# Vertical.net
KiCad netlist of a schematic drawn in Altium Designer
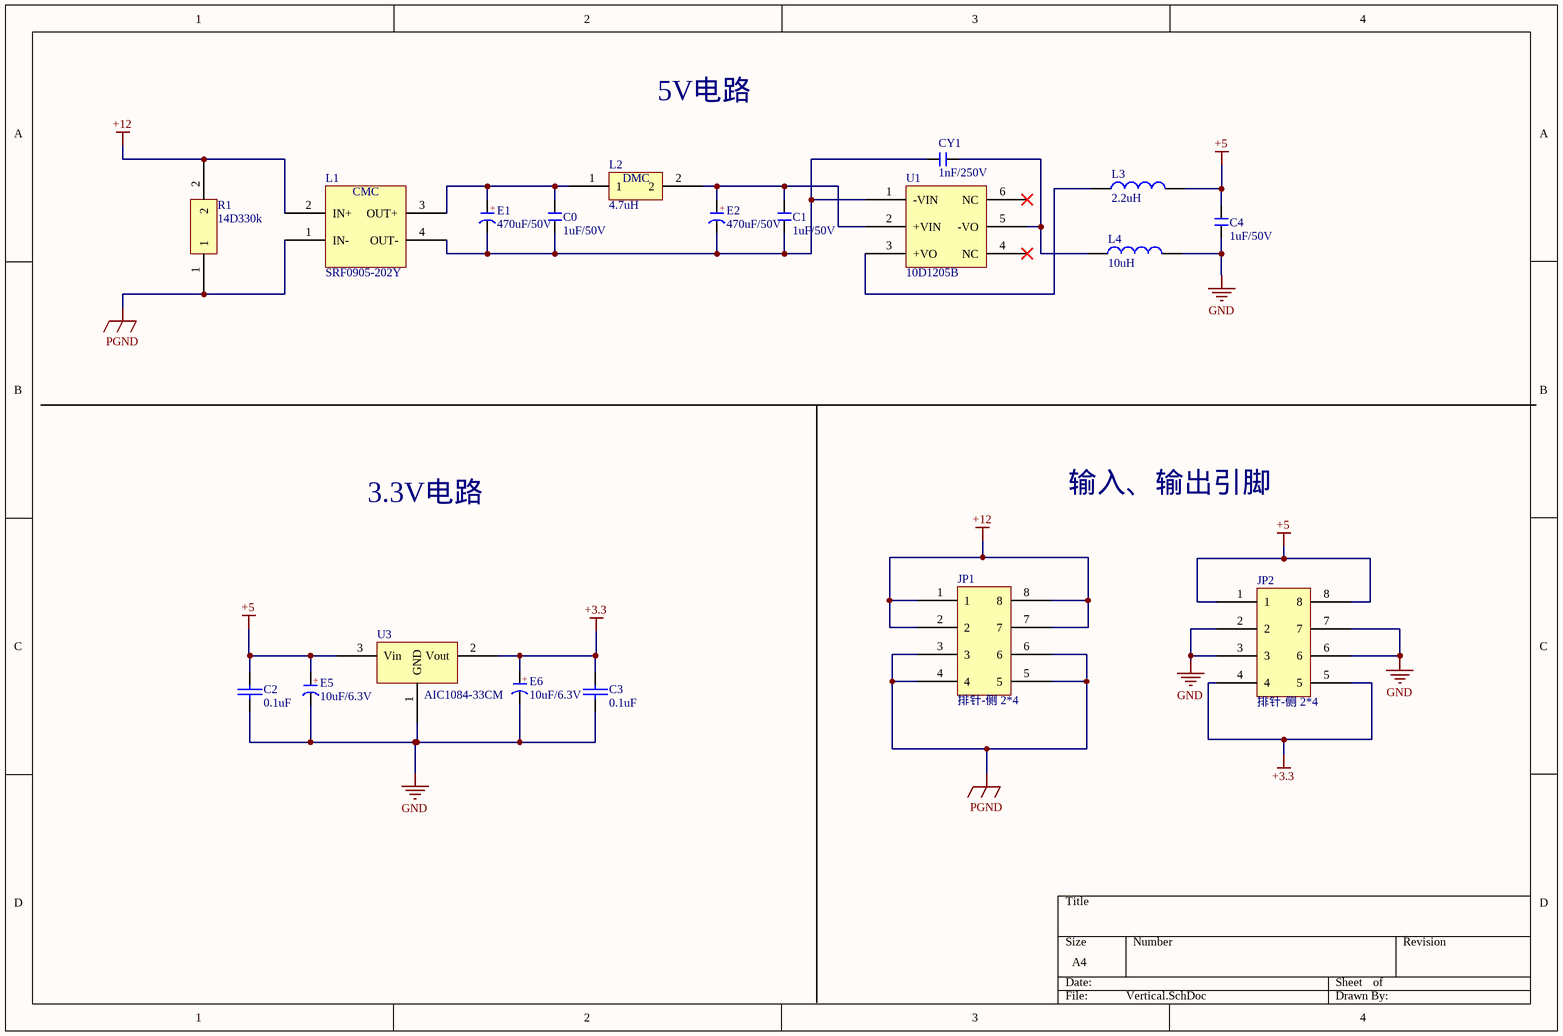
[diagram p0: Vertical.SchDoc]

(export (version "E")
  (design (tool "Eeschema 10.0.6"))
  (components
    (comp (ref "C0")
      (value "1uF/50V")
      (footprint "CC 2.2*5")
      (description "直插瓷片电容")
      (fields (field (name "版权归属") "源创客"))
      (libsource (lib "3.1   - 电阻-电容-电感") (part "C-CC"))
    )
    (comp (ref "C1")
      (value "1uF/50V")
      (footprint "CC 2.2*5")
      (description "直插瓷片电容")
      (fields (field (name "版权归属") "源创客"))
      (libsource (lib "3.1   - 电阻-电容-电感") (part "C-CC"))
    )
    (comp (ref "C2")
      (value "0.1uF")
      (footprint "0603C")
      (description "无极性电容")
      (libsource (lib "电容") (part "CAP"))
    )
    (comp (ref "C3")
      (value "0.1uF")
      (footprint "0603C")
      (description "无极性电容")
      (libsource (lib "电容") (part "CAP"))
    )
    (comp (ref "C4")
      (value "1uF/50V")
      (footprint "CC 2.2*5")
      (description "直插瓷片电容")
      (fields (field (name "版权归属") "源创客"))
      (libsource (lib "3.1   - 电阻-电容-电感") (part "C-CC"))
    )
    (comp (ref "CY1")
      (value "1nF/250V")
      (footprint "CY 7.5*10*4")
      (description "高压陶瓷电容，Y电容")
      (fields (field (name "版权归属") "源创客"))
      (libsource (lib "3.1   - 电阻-电容-电感") (part "C-CY"))
    )
    (comp (ref "E1")
      (value "470uF/50V")
      (footprint "CM G(12.5*13.5)")
      (description "贴片电解电容")
      (fields (field (name "版权归属") "源创客"))
      (libsource (lib "3.1   - 电阻-电容-电感") (part "C-CM"))
    )
    (comp (ref "E2")
      (value "470uF/50V")
      (footprint "CM G(12.5*13.5)")
      (description "贴片电解电容")
      (fields (field (name "版权归属") "源创客"))
      (libsource (lib "3.1   - 电阻-电容-电感") (part "C-CM"))
    )
    (comp (ref "E5")
      (value "10uF/6.3V")
      (footprint "CD A(3216)")
      (description "贴片钽电容")
      (fields (field (name "版权归属") "源创客"))
      (libsource (lib "3.1   - 电阻-电容-电感") (part "C-CD"))
    )
    (comp (ref "E6")
      (value "10uF/6.3V")
      (footprint "CD A(3216)")
      (description "贴片钽电容")
      (fields (field (name "版权归属") "源创客"))
      (libsource (lib "3.1   - 电阻-电容-电感") (part "C-CD"))
    )
    (comp (ref "JP1") (value "排针-侧 2*4") (footprint "排针-侧 2*4") (libsource (lib "power") (part "排针-侧 2*4")))
    (comp (ref "JP2") (value "排针-侧 2*4") (footprint "排针-侧 2*4") (libsource (lib "power") (part "排针-侧 2*4")))
    (comp (ref "L1")
      (value "SRF0905-202Y")
      (footprint "SRF0905")
      (description "共模电感")
      (libsource (lib "power") (part "SRF0905-202Y"))
    )
    (comp (ref "L2")
      (value "4.7uH")
      (footprint "NR5020")
      (description "差模电感")
      (libsource (lib "power") (part "DML-5020"))
    )
    (comp (ref "L3")
      (value "2.2uH")
      (footprint "L 0805")
      (description "小功率贴片电感")
      (fields (field (name "版权归属") "源创客"))
      (libsource (lib "3.1   - 电阻-电容-电感") (part "L"))
    )
    (comp (ref "L4")
      (value "10uH")
      (footprint "L 0805")
      (description "小功率贴片电感")
      (fields (field (name "版权归属") "源创客"))
      (libsource (lib "3.1   - 电阻-电容-电感") (part "L"))
    )
    (comp (ref "R1") (value "14D330k") (footprint "14D330k") (libsource (lib "power") (part "14D330k")))
    (comp (ref "U1") (value "10D1205B") (footprint "10D1205B") (libsource (lib "power") (part "10D1205B")))
    (comp (ref "U3")
      (value "AIC1084-33CM")
      (footprint "TO263-3B")
      (libsource (lib "power") (part "AIC1084-33CM"))
    )
  )
  (nets
    (net (code "1") (name "+3.3") (class "Default")
      (node (ref "C3") (pin "1") (pinfunction "1_1") (pintype "passive"))
      (node (ref "E6") (pin "1") (pinfunction "A_1") (pintype "passive"))
      (node (ref "JP2") (pin "4") (pinfunction "4_4") (pintype "passive"))
      (node (ref "JP2") (pin "5") (pinfunction "5_5") (pintype "passive"))
      (node (ref "U3") (pin "2") (pinfunction "Vout_2") (pintype "passive"))
    )
    (net (code "2") (name "+5") (class "Default")
      (node (ref "C2") (pin "2") (pinfunction "2_2") (pintype "passive"))
      (node (ref "C4") (pin "1") (pinfunction "1_1") (pintype "passive"))
      (node (ref "E5") (pin "1") (pinfunction "A_1") (pintype "passive"))
      (node (ref "JP2") (pin "1") (pinfunction "1_1") (pintype "passive"))
      (node (ref "JP2") (pin "8") (pinfunction "8_8") (pintype "passive"))
      (node (ref "L3") (pin "2") (pinfunction "2_2") (pintype "passive"))
      (node (ref "U3") (pin "3") (pinfunction "Vin_3") (pintype "passive"))
    )
    (net (code "3") (name "+12") (class "Default")
      (node (ref "JP1") (pin "1") (pinfunction "1_1") (pintype "passive"))
      (node (ref "JP1") (pin "2") (pinfunction "2_2") (pintype "passive"))
      (node (ref "JP1") (pin "7") (pinfunction "7_7") (pintype "passive"))
      (node (ref "JP1") (pin "8") (pinfunction "8_8") (pintype "passive"))
      (node (ref "L1") (pin "2") (pinfunction "IN+_2") (pintype "passive"))
      (node (ref "R1") (pin "2") (pinfunction "2_2") (pintype "passive"))
    )
    (net (code "4") (name "GND") (class "Default")
      (node (ref "C2") (pin "1") (pinfunction "1_1") (pintype "passive"))
      (node (ref "C3") (pin "2") (pinfunction "2_2") (pintype "passive"))
      (node (ref "C4") (pin "2") (pinfunction "2_2") (pintype "passive"))
      (node (ref "E5") (pin "2") (pinfunction "K_2") (pintype "passive"))
      (node (ref "E6") (pin "2") (pinfunction "K_2") (pintype "passive"))
      (node (ref "JP2") (pin "2") (pinfunction "2_2") (pintype "passive"))
      (node (ref "JP2") (pin "3") (pinfunction "3_3") (pintype "passive"))
      (node (ref "JP2") (pin "6") (pinfunction "6_6") (pintype "passive"))
      (node (ref "JP2") (pin "7") (pinfunction "7_7") (pintype "passive"))
      (node (ref "L4") (pin "2") (pinfunction "2_2") (pintype "passive"))
      (node (ref "U3") (pin "1") (pinfunction "GND_1") (pintype "passive"))
    )
    (net (code "5") (name "Net-(E1-A)") (class "Default")
      (node (ref "C0") (pin "1") (pinfunction "1_1") (pintype "passive"))
      (node (ref "E1") (pin "1") (pinfunction "A_1") (pintype "passive"))
      (node (ref "L1") (pin "3") (pinfunction "OUT+_3") (pintype "passive"))
      (node (ref "L2") (pin "1") (pinfunction "1_1") (pintype "passive"))
    )
    (net (code "6") (name "Net-(E1-K)") (class "Default")
      (node (ref "C0") (pin "2") (pinfunction "2_2") (pintype "passive"))
      (node (ref "C1") (pin "2") (pinfunction "2_2") (pintype "passive"))
      (node (ref "CY1") (pin "1") (pinfunction "1_1") (pintype "passive"))
      (node (ref "E1") (pin "2") (pinfunction "K_2") (pintype "passive"))
      (node (ref "E2") (pin "2") (pinfunction "K_2") (pintype "passive"))
      (node (ref "L1") (pin "4") (pinfunction "OUT-_4") (pintype "passive"))
      (node (ref "U1") (pin "1") (pinfunction "-VIN_1") (pintype "passive"))
    )
    (net (code "7") (name "Net-(E2-A)") (class "Default")
      (node (ref "C1") (pin "1") (pinfunction "1_1") (pintype "passive"))
      (node (ref "E2") (pin "1") (pinfunction "A_1") (pintype "passive"))
      (node (ref "L2") (pin "2") (pinfunction "2_2") (pintype "passive"))
      (node (ref "U1") (pin "2") (pinfunction "+VIN_2") (pintype "passive"))
    )
    (net (code "8") (name "Net-(U1-+VO)") (class "Default")
      (node (ref "L3") (pin "1") (pinfunction "1_1") (pintype "passive"))
      (node (ref "U1") (pin "3") (pinfunction "+VO_3") (pintype "passive"))
    )
    (net (code "9") (name "Net-(U1--VO)") (class "Default")
      (node (ref "CY1") (pin "2") (pinfunction "2_2") (pintype "passive"))
      (node (ref "L4") (pin "1") (pinfunction "1_1") (pintype "passive"))
      (node (ref "U1") (pin "5") (pinfunction "-VO_5") (pintype "passive"))
    )
    (net (code "10") (name "PGND") (class "Default")
      (node (ref "JP1") (pin "3") (pinfunction "3_3") (pintype "passive"))
      (node (ref "JP1") (pin "4") (pinfunction "4_4") (pintype "passive"))
      (node (ref "JP1") (pin "5") (pinfunction "5_5") (pintype "passive"))
      (node (ref "JP1") (pin "6") (pinfunction "6_6") (pintype "passive"))
      (node (ref "L1") (pin "1") (pinfunction "IN-_1") (pintype "passive"))
      (node (ref "R1") (pin "1") (pinfunction "1_1") (pintype "passive"))
    )
    (net (code "11") (name "unconnected-(U1-NC-Pad4)") (class "Default")
      (node (ref "U1") (pin "4") (pinfunction "NC_4") (pintype "passive+no_connect"))
    )
    (net (code "12") (name "unconnected-(U1-NC-Pad6)") (class "Default")
      (node (ref "U1") (pin "6") (pinfunction "NC_6") (pintype "passive+no_connect"))
    )
  )
)
